# Sheet4.net
KiCad netlist of a schematic drawn in Altium Designer
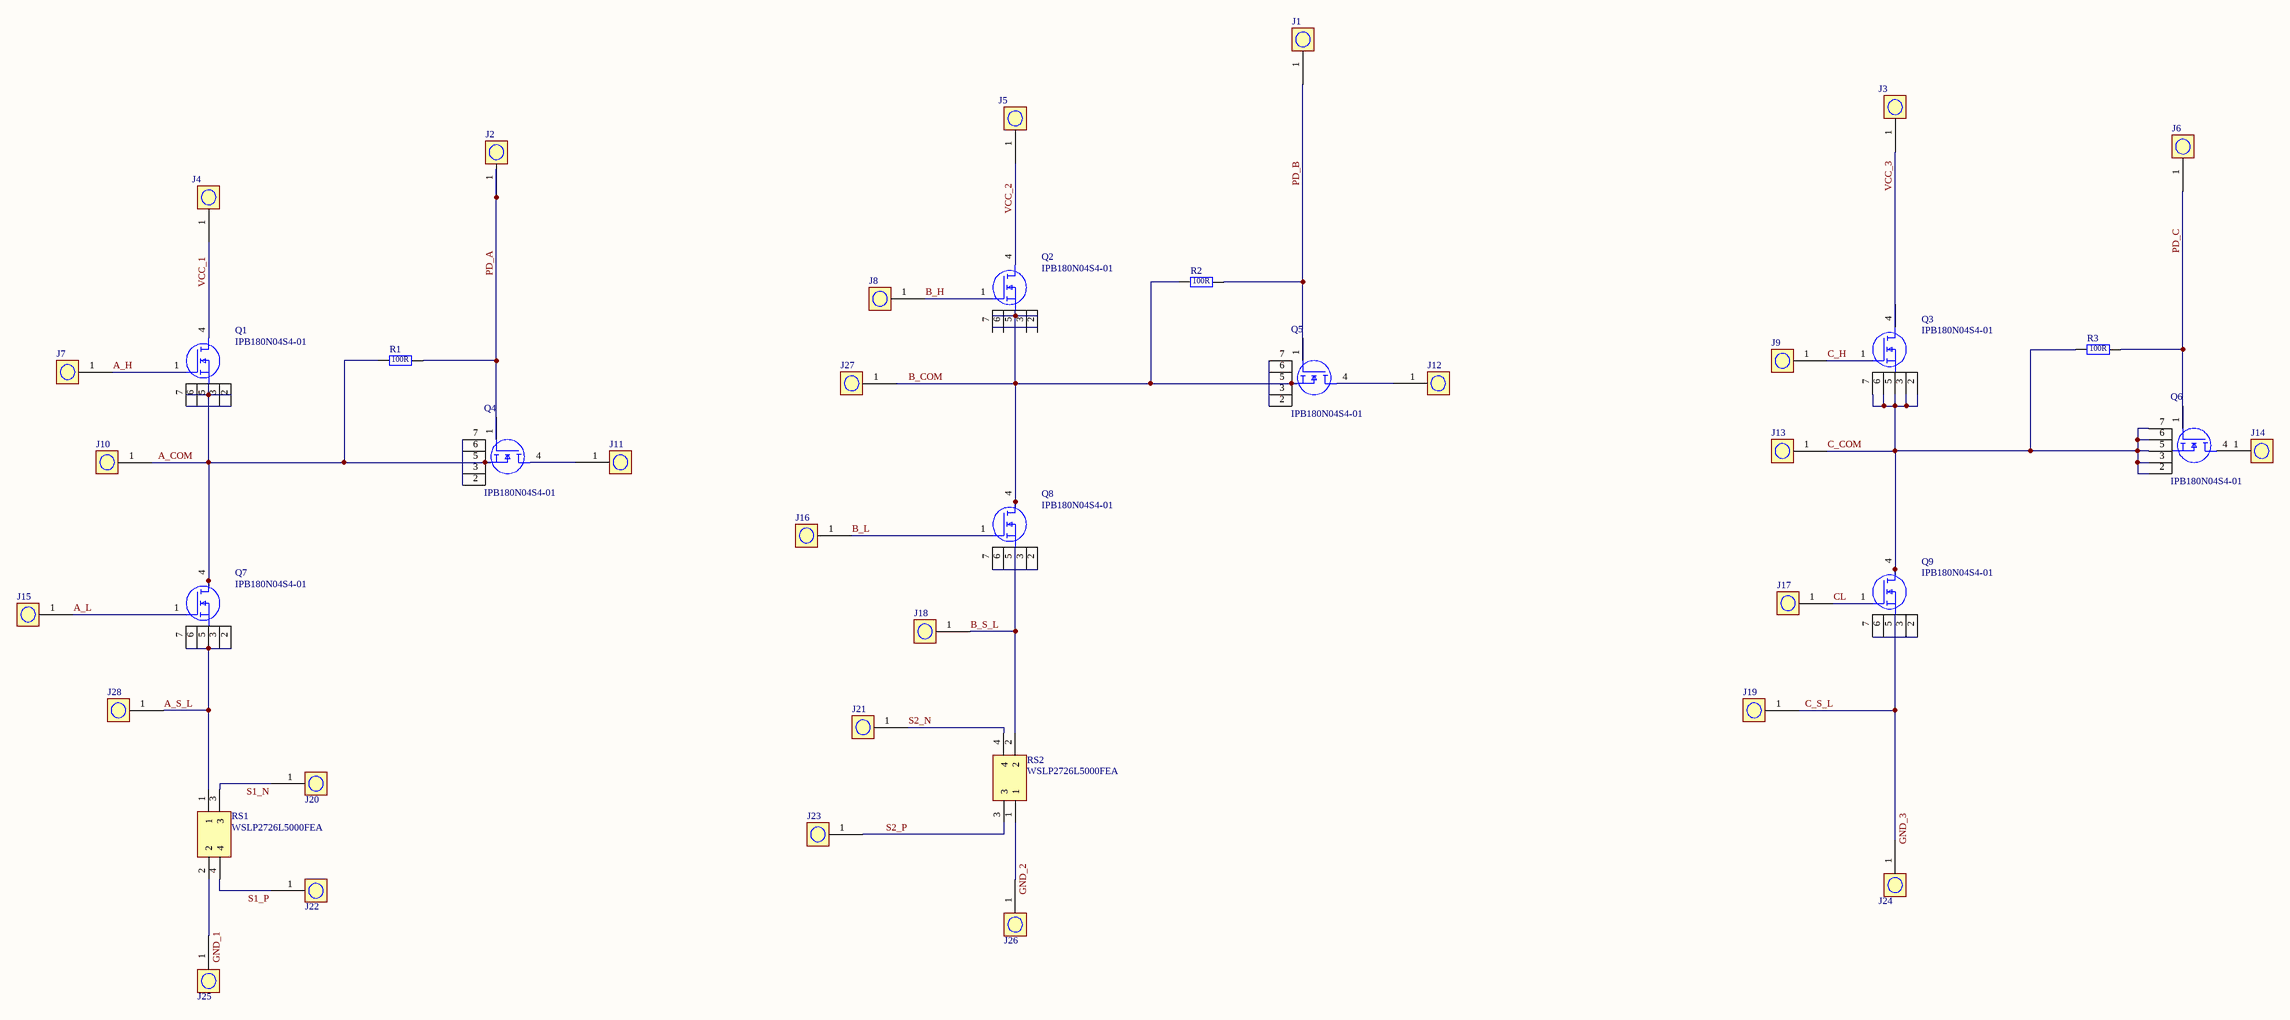
[diagram p0: Sheet4.SchDoc]

(export (version "E")
  (design (tool "Eeschema 10.0.6"))
  (components
    (comp (ref "J1")
      (value "CON_SMD_SMALL")
      (footprint "CONN_SMALL")
      (libsource (lib "") (part "CON_SMD_SMALL_2"))
    )
    (comp (ref "J2")
      (value "CON_SMD_SMALL")
      (footprint "CONN_SMALL")
      (libsource (lib "") (part "CON_SMD_SMALL_2"))
    )
    (comp (ref "J3")
      (value "CON_SMD_SMALL")
      (footprint "CONN_SMALL")
      (libsource (lib "") (part "CON_SMD_SMALL_2"))
    )
    (comp (ref "J4")
      (value "CON_SMD_SMALL")
      (footprint "CONN_SMALL")
      (libsource (lib "") (part "CON_SMD_SMALL_2"))
    )
    (comp (ref "J5")
      (value "CON_SMD_SMALL")
      (footprint "CONN_SMALL")
      (libsource (lib "") (part "CON_SMD_SMALL_2"))
    )
    (comp (ref "J6")
      (value "CON_SMD_SMALL")
      (footprint "CONN_SMALL")
      (libsource (lib "") (part "CON_SMD_SMALL_2"))
    )
    (comp (ref "J7")
      (value "CON_SMD_SMALL")
      (footprint "CONN_SMALL")
      (libsource (lib "") (part "CON_SMD_SMALL_1"))
    )
    (comp (ref "J8")
      (value "CON_SMD_SMALL")
      (footprint "CONN_SMALL")
      (libsource (lib "") (part "CON_SMD_SMALL_1"))
    )
    (comp (ref "J9")
      (value "CON_SMD_SMALL")
      (footprint "CONN_SMALL")
      (libsource (lib "") (part "CON_SMD_SMALL_1"))
    )
    (comp (ref "J10")
      (value "CON_SMD_SMALL")
      (footprint "CONN_SMALL")
      (libsource (lib "") (part "CON_SMD_SMALL_1"))
    )
    (comp (ref "J11")
      (value "CON_SMD_SMALL")
      (footprint "CONN_SMALL")
      (libsource (lib "MyPCBlib") (part "CON_SMD_SMALL"))
    )
    (comp (ref "J12")
      (value "CON_SMD_SMALL")
      (footprint "CONN_SMALL")
      (libsource (lib "MyPCBlib") (part "CON_SMD_SMALL"))
    )
    (comp (ref "J13")
      (value "CON_SMD_SMALL")
      (footprint "CONN_SMALL")
      (libsource (lib "") (part "CON_SMD_SMALL_1"))
    )
    (comp (ref "J14")
      (value "CON_SMD_SMALL")
      (footprint "CONN_SMALL")
      (libsource (lib "MyPCBlib") (part "CON_SMD_SMALL"))
    )
    (comp (ref "J15")
      (value "CON_SMD_SMALL")
      (footprint "CONN_SMALL")
      (libsource (lib "") (part "CON_SMD_SMALL_1"))
    )
    (comp (ref "J16")
      (value "CON_SMD_SMALL")
      (footprint "CONN_SMALL")
      (libsource (lib "") (part "CON_SMD_SMALL_1"))
    )
    (comp (ref "J17")
      (value "CON_SMD_SMALL")
      (footprint "CONN_SMALL")
      (libsource (lib "") (part "CON_SMD_SMALL_1"))
    )
    (comp (ref "J18")
      (value "CON_SMD_SMALL")
      (footprint "CONN_SMALL")
      (libsource (lib "") (part "CON_SMD_SMALL_1"))
    )
    (comp (ref "J19")
      (value "CON_SMD_SMALL")
      (footprint "CONN_SMALL")
      (libsource (lib "") (part "CON_SMD_SMALL_1"))
    )
    (comp (ref "J20")
      (value "CON_SMD_SMALL")
      (footprint "CONN_SMALL")
      (libsource (lib "MyPCBlib") (part "CON_SMD_SMALL"))
    )
    (comp (ref "J21")
      (value "CON_SMD_SMALL")
      (footprint "CONN_SMALL")
      (libsource (lib "") (part "CON_SMD_SMALL_1"))
    )
    (comp (ref "J22")
      (value "CON_SMD_SMALL")
      (footprint "CONN_SMALL")
      (libsource (lib "MyPCBlib") (part "CON_SMD_SMALL"))
    )
    (comp (ref "J23")
      (value "CON_SMD_SMALL")
      (footprint "CONN_SMALL")
      (libsource (lib "") (part "CON_SMD_SMALL_1"))
    )
    (comp (ref "J24")
      (value "CON_SMD_SMALL")
      (footprint "CON_BIG")
      (libsource (lib "") (part "CON_SMD_SMALL_3"))
    )
    (comp (ref "J25")
      (value "CON_SMD_SMALL")
      (footprint "CONN_SMALL")
      (libsource (lib "") (part "CON_SMD_SMALL_3"))
    )
    (comp (ref "J26")
      (value "CON_SMD_SMALL")
      (footprint "CONN_SMALL")
      (libsource (lib "") (part "CON_SMD_SMALL_3"))
    )
    (comp (ref "J27")
      (value "CON_SMD_SMALL")
      (footprint "CONN_SMALL")
      (libsource (lib "") (part "CON_SMD_SMALL_1"))
    )
    (comp (ref "J28")
      (value "CON_SMD_SMALL")
      (footprint "CONN_SMALL")
      (libsource (lib "") (part "CON_SMD_SMALL_1"))
    )
    (comp (ref "Q1")
      (value "IPB180N04S4-01")
      (footprint "SamacSys:IPB240N04S4R9ATMA1")
      (description "MOSFET (N-Channel)")
      (fields (field (name "MOUSER PART NUMBER") "726-IPB180N04S4-01"))
      (libsource (lib "SamacSys") (part "IPB180N04S4-01"))
    )
    (comp (ref "Q2")
      (value "IPB180N04S4-01")
      (footprint "SamacSys:IPB240N04S4R9ATMA1")
      (description "MOSFET (N-Channel)")
      (fields (field (name "MOUSER PART NUMBER") "726-IPB180N04S4-01"))
      (libsource (lib "SamacSys") (part "IPB180N04S4-01"))
    )
    (comp (ref "Q3")
      (value "IPB180N04S4-01")
      (footprint "SamacSys:IPB240N04S4R9ATMA1")
      (description "MOSFET (N-Channel)")
      (fields (field (name "MOUSER PART NUMBER") "726-IPB180N04S4-01"))
      (libsource (lib "SamacSys") (part "IPB180N04S4-01"))
    )
    (comp (ref "Q4")
      (value "IPB180N04S4-01")
      (footprint "SamacSys:IPB240N04S4R9ATMA1")
      (description "MOSFET (N-Channel)")
      (fields (field (name "MOUSER PART NUMBER") "726-IPB180N04S4-01"))
      (libsource (lib "SamacSys") (part "IPB180N04S4-01"))
    )
    (comp (ref "Q5")
      (value "IPB180N04S4-01")
      (footprint "SamacSys:IPB240N04S4R9ATMA1")
      (description "MOSFET (N-Channel)")
      (fields (field (name "MOUSER PART NUMBER") "726-IPB180N04S4-01"))
      (libsource (lib "SamacSys") (part "IPB180N04S4-01"))
    )
    (comp (ref "Q6")
      (value "IPB180N04S4-01")
      (footprint "SamacSys:IPB240N04S4R9ATMA1")
      (description "MOSFET (N-Channel)")
      (fields (field (name "MOUSER PART NUMBER") "726-IPB180N04S4-01"))
      (libsource (lib "SamacSys") (part "IPB180N04S4-01"))
    )
    (comp (ref "Q7")
      (value "IPB180N04S4-01")
      (footprint "SamacSys:IPB240N04S4R9ATMA1")
      (description "MOSFET (N-Channel)")
      (fields (field (name "MOUSER PART NUMBER") "726-IPB180N04S4-01"))
      (libsource (lib "SamacSys") (part "IPB180N04S4-01"))
    )
    (comp (ref "Q8")
      (value "IPB180N04S4-01")
      (footprint "SamacSys:IPB240N04S4R9ATMA1")
      (description "MOSFET (N-Channel)")
      (fields (field (name "MOUSER PART NUMBER") "726-IPB180N04S4-01"))
      (libsource (lib "SamacSys") (part "IPB180N04S4-01"))
    )
    (comp (ref "Q9")
      (value "IPB180N04S4-01")
      (footprint "SamacSys:IPB240N04S4R9ATMA1")
      (description "MOSFET (N-Channel)")
      (fields (field (name "MOUSER PART NUMBER") "726-IPB180N04S4-01"))
      (libsource (lib "SamacSys") (part "IPB180N04S4-01"))
    )
    (comp (ref "R1")
      (value "100R")
      (footprint "RESC1608X06N")
      (fields (field (name "Comment") "R"))
      (libsource (lib "MyPCBlib") (part "R"))
    )
    (comp (ref "R2")
      (value "100R")
      (footprint "RESC1608X06N")
      (fields (field (name "Comment") "R"))
      (libsource (lib "MyPCBlib") (part "R"))
    )
    (comp (ref "R3")
      (value "100R")
      (footprint "RESC1608X06N")
      (fields (field (name "Comment") "R"))
      (libsource (lib "MyPCBlib") (part "R"))
    )
    (comp (ref "RS1")
      (value "WSLP2726L5000FEA")
      (footprint "SamacSys:WSL27261L000FEA")
      (description "Resistor")
      (fields (field (name "MOUSER PART NUMBER") "71-WSLP2726L5000FEA"))
      (libsource (lib "") (part "WSLP2726L5000FEA_1"))
    )
    (comp (ref "RS2")
      (value "WSLP2726L5000FEA")
      (footprint "SamacSys:WSL27261L000FEA")
      (description "Resistor")
      (fields (field (name "MOUSER PART NUMBER") "71-WSLP2726L5000FEA"))
      (libsource (lib "SamacSys") (part "WSLP2726L5000FEA"))
    )
  )
  (nets
    (net (code "1") (name "/A_COM") (class "Default")
      (node (ref "J10") (pin "1") (pinfunction "1_1") (pintype "passive"))
      (node (ref "Q1") (pin "5") (pinfunction "S_3_5") (pintype "passive"))
      (node (ref "Q4") (pin "5") (pinfunction "S_3_5") (pintype "passive"))
      (node (ref "Q7") (pin "4") (pinfunction "D_4") (pintype "passive"))
      (node (ref "R1") (pin "1") (pinfunction "1_1") (pintype "passive"))
    )
    (net (code "2") (name "/A_H") (class "Default")
      (node (ref "J7") (pin "1") (pinfunction "1_1") (pintype "passive"))
      (node (ref "Q1") (pin "1") (pinfunction "G_1") (pintype "passive"))
    )
    (net (code "3") (name "/A_L") (class "Default")
      (node (ref "J15") (pin "1") (pinfunction "1_1") (pintype "passive"))
      (node (ref "Q7") (pin "1") (pinfunction "G_1") (pintype "passive"))
    )
    (net (code "4") (name "/A_S_L") (class "Default")
      (node (ref "J28") (pin "1") (pinfunction "1_1") (pintype "passive"))
      (node (ref "RS1") (pin "1") (pinfunction "1_1") (pintype "passive"))
    )
    (net (code "5") (name "/B_COM") (class "Default")
      (node (ref "J27") (pin "1") (pinfunction "1_1") (pintype "passive"))
      (node (ref "Q2") (pin "5") (pinfunction "S_3_5") (pintype "passive"))
      (node (ref "Q5") (pin "5") (pinfunction "S_3_5") (pintype "passive"))
      (node (ref "Q8") (pin "4") (pinfunction "D_4") (pintype "passive"))
      (node (ref "R2") (pin "1") (pinfunction "1_1") (pintype "passive"))
    )
    (net (code "6") (name "/B_H") (class "Default")
      (node (ref "J8") (pin "1") (pinfunction "1_1") (pintype "passive"))
      (node (ref "Q2") (pin "1") (pinfunction "G_1") (pintype "passive"))
    )
    (net (code "7") (name "/B_L") (class "Default")
      (node (ref "J16") (pin "1") (pinfunction "1_1") (pintype "passive"))
      (node (ref "Q8") (pin "1") (pinfunction "G_1") (pintype "passive"))
    )
    (net (code "8") (name "/B_S_L") (class "Default")
      (node (ref "J18") (pin "1") (pinfunction "1_1") (pintype "passive"))
      (node (ref "Q8") (pin "5") (pinfunction "S_3_5") (pintype "passive"))
      (node (ref "RS2") (pin "2") (pinfunction "2_2") (pintype "passive"))
    )
    (net (code "9") (name "/CL") (class "Default")
      (node (ref "J17") (pin "1") (pinfunction "1_1") (pintype "passive"))
      (node (ref "Q9") (pin "1") (pinfunction "G_1") (pintype "passive"))
    )
    (net (code "10") (name "/C_COM") (class "Default")
      (node (ref "J13") (pin "1") (pinfunction "1_1") (pintype "passive"))
      (node (ref "Q9") (pin "4") (pinfunction "D_4") (pintype "passive"))
      (node (ref "R3") (pin "1") (pinfunction "1_1") (pintype "passive"))
    )
    (net (code "11") (name "/C_H") (class "Default")
      (node (ref "J9") (pin "1") (pinfunction "1_1") (pintype "passive"))
      (node (ref "Q3") (pin "1") (pinfunction "G_1") (pintype "passive"))
    )
    (net (code "12") (name "/C_S_L") (class "Default")
      (node (ref "J19") (pin "1") (pinfunction "1_1") (pintype "passive"))
      (node (ref "J24") (pin "1") (pinfunction "1_1") (pintype "passive"))
      (node (ref "Q9") (pin "5") (pinfunction "S_3_5") (pintype "passive"))
    )
    (net (code "13") (name "/GND_1") (class "Default")
      (node (ref "J25") (pin "1") (pinfunction "1_1") (pintype "passive"))
      (node (ref "RS1") (pin "2") (pinfunction "2_2") (pintype "passive"))
    )
    (net (code "14") (name "/GND_2") (class "Default")
      (node (ref "J26") (pin "1") (pinfunction "1_1") (pintype "passive"))
      (node (ref "RS2") (pin "1") (pinfunction "1_1") (pintype "passive"))
    )
    (net (code "15") (name "/PD_A") (class "Default")
      (node (ref "J2") (pin "1") (pinfunction "1_1") (pintype "passive"))
      (node (ref "Q4") (pin "1") (pinfunction "G_1") (pintype "passive"))
      (node (ref "R1") (pin "2") (pinfunction "2_2") (pintype "passive"))
    )
    (net (code "16") (name "/PD_B") (class "Default")
      (node (ref "J1") (pin "1") (pinfunction "1_1") (pintype "passive"))
      (node (ref "Q5") (pin "1") (pinfunction "G_1") (pintype "passive"))
      (node (ref "R2") (pin "2") (pinfunction "2_2") (pintype "passive"))
    )
    (net (code "17") (name "/PD_C") (class "Default")
      (node (ref "J6") (pin "1") (pinfunction "1_1") (pintype "passive"))
      (node (ref "Q6") (pin "1") (pinfunction "G_1") (pintype "passive"))
      (node (ref "R3") (pin "2") (pinfunction "2_2") (pintype "passive"))
    )
    (net (code "18") (name "/S1_N") (class "Default")
      (node (ref "J20") (pin "1") (pinfunction "1_1") (pintype "passive"))
      (node (ref "RS1") (pin "3") (pinfunction "3_3") (pintype "passive"))
    )
    (net (code "19") (name "/S1_P") (class "Default")
      (node (ref "J22") (pin "1") (pinfunction "1_1") (pintype "passive"))
      (node (ref "RS1") (pin "4") (pinfunction "4_4") (pintype "passive"))
    )
    (net (code "20") (name "/S2_N") (class "Default")
      (node (ref "J21") (pin "1") (pinfunction "1_1") (pintype "passive"))
      (node (ref "RS2") (pin "4") (pinfunction "4_4") (pintype "passive"))
    )
    (net (code "21") (name "/S2_P") (class "Default")
      (node (ref "J23") (pin "1") (pinfunction "1_1") (pintype "passive"))
      (node (ref "RS2") (pin "3") (pinfunction "3_3") (pintype "passive"))
    )
    (net (code "22") (name "/VCC_1") (class "Default")
      (node (ref "J4") (pin "1") (pinfunction "1_1") (pintype "passive"))
      (node (ref "Q1") (pin "4") (pinfunction "D_4") (pintype "passive"))
    )
    (net (code "23") (name "/VCC_2") (class "Default")
      (node (ref "J5") (pin "1") (pinfunction "1_1") (pintype "passive"))
      (node (ref "Q2") (pin "4") (pinfunction "D_4") (pintype "passive"))
    )
    (net (code "24") (name "/VCC_3") (class "Default")
      (node (ref "J3") (pin "1") (pinfunction "1_1") (pintype "passive"))
      (node (ref "Q3") (pin "4") (pinfunction "D_4") (pintype "passive"))
    )
    (net (code "25") (name "Net-(Q4-D)") (class "Default")
      (node (ref "J11") (pin "1") (pinfunction "1_1") (pintype "passive"))
      (node (ref "Q4") (pin "4") (pinfunction "D_4") (pintype "passive"))
    )
    (net (code "26") (name "Net-(Q5-D)") (class "Default")
      (node (ref "J12") (pin "1") (pinfunction "1_1") (pintype "passive"))
      (node (ref "Q5") (pin "4") (pinfunction "D_4") (pintype "passive"))
    )
    (net (code "27") (name "Net-(Q6-D)") (class "Default")
      (node (ref "J14") (pin "1") (pinfunction "1_1") (pintype "passive"))
      (node (ref "Q6") (pin "4") (pinfunction "D_4") (pintype "passive"))
    )
    (net (code "28") (name "unconnected-(Q1-S_1-Pad2)") (class "Default")
      (node (ref "Q1") (pin "2") (pinfunction "S_1_2") (pintype "passive"))
    )
    (net (code "29") (name "unconnected-(Q1-S_2-Pad3)") (class "Default")
      (node (ref "Q1") (pin "3") (pinfunction "S_2_3") (pintype "passive"))
    )
    (net (code "30") (name "unconnected-(Q1-S_4-Pad6)") (class "Default")
      (node (ref "Q1") (pin "6") (pinfunction "S_4_6") (pintype "passive"))
    )
    (net (code "31") (name "unconnected-(Q1-S_5-Pad7)") (class "Default")
      (node (ref "Q1") (pin "7") (pinfunction "S_5_7") (pintype "passive"))
    )
    (net (code "32") (name "unconnected-(Q2-S_1-Pad2)") (class "Default")
      (node (ref "Q2") (pin "2") (pinfunction "S_1_2") (pintype "passive"))
    )
    (net (code "33") (name "unconnected-(Q2-S_2-Pad3)") (class "Default")
      (node (ref "Q2") (pin "3") (pinfunction "S_2_3") (pintype "passive"))
    )
    (net (code "34") (name "unconnected-(Q2-S_4-Pad6)") (class "Default")
      (node (ref "Q2") (pin "6") (pinfunction "S_4_6") (pintype "passive"))
    )
    (net (code "35") (name "unconnected-(Q2-S_5-Pad7)") (class "Default")
      (node (ref "Q2") (pin "7") (pinfunction "S_5_7") (pintype "passive"))
    )
    (net (code "36") (name "unconnected-(Q3-S_1-Pad2)") (class "Default")
      (node (ref "Q3") (pin "2") (pinfunction "S_1_2") (pintype "passive"))
    )
    (net (code "37") (name "unconnected-(Q3-S_2-Pad3)") (class "Default")
      (node (ref "Q3") (pin "3") (pinfunction "S_2_3") (pintype "passive"))
    )
    (net (code "38") (name "unconnected-(Q3-S_3-Pad5)") (class "Default")
      (node (ref "Q3") (pin "5") (pinfunction "S_3_5") (pintype "passive"))
    )
    (net (code "39") (name "unconnected-(Q3-S_4-Pad6)") (class "Default")
      (node (ref "Q3") (pin "6") (pinfunction "S_4_6") (pintype "passive"))
    )
    (net (code "40") (name "unconnected-(Q3-S_5-Pad7)") (class "Default")
      (node (ref "Q3") (pin "7") (pinfunction "S_5_7") (pintype "passive"))
    )
    (net (code "41") (name "unconnected-(Q4-S_1-Pad2)") (class "Default")
      (node (ref "Q4") (pin "2") (pinfunction "S_1_2") (pintype "passive"))
    )
    (net (code "42") (name "unconnected-(Q4-S_2-Pad3)") (class "Default")
      (node (ref "Q4") (pin "3") (pinfunction "S_2_3") (pintype "passive"))
    )
    (net (code "43") (name "unconnected-(Q4-S_4-Pad6)") (class "Default")
      (node (ref "Q4") (pin "6") (pinfunction "S_4_6") (pintype "passive"))
    )
    (net (code "44") (name "unconnected-(Q4-S_5-Pad7)") (class "Default")
      (node (ref "Q4") (pin "7") (pinfunction "S_5_7") (pintype "passive"))
    )
    (net (code "45") (name "unconnected-(Q5-S_1-Pad2)") (class "Default")
      (node (ref "Q5") (pin "2") (pinfunction "S_1_2") (pintype "passive"))
    )
    (net (code "46") (name "unconnected-(Q5-S_2-Pad3)") (class "Default")
      (node (ref "Q5") (pin "3") (pinfunction "S_2_3") (pintype "passive"))
    )
    (net (code "47") (name "unconnected-(Q5-S_4-Pad6)") (class "Default")
      (node (ref "Q5") (pin "6") (pinfunction "S_4_6") (pintype "passive"))
    )
    (net (code "48") (name "unconnected-(Q5-S_5-Pad7)") (class "Default")
      (node (ref "Q5") (pin "7") (pinfunction "S_5_7") (pintype "passive"))
    )
    (net (code "49") (name "unconnected-(Q6-S_1-Pad2)") (class "Default")
      (node (ref "Q6") (pin "2") (pinfunction "S_1_2") (pintype "passive"))
    )
    (net (code "50") (name "unconnected-(Q6-S_2-Pad3)") (class "Default")
      (node (ref "Q6") (pin "3") (pinfunction "S_2_3") (pintype "passive"))
    )
    (net (code "51") (name "unconnected-(Q6-S_3-Pad5)") (class "Default")
      (node (ref "Q6") (pin "5") (pinfunction "S_3_5") (pintype "passive"))
    )
    (net (code "52") (name "unconnected-(Q6-S_4-Pad6)") (class "Default")
      (node (ref "Q6") (pin "6") (pinfunction "S_4_6") (pintype "passive"))
    )
    (net (code "53") (name "unconnected-(Q6-S_5-Pad7)") (class "Default")
      (node (ref "Q6") (pin "7") (pinfunction "S_5_7") (pintype "passive"))
    )
    (net (code "54") (name "unconnected-(Q7-S_1-Pad2)") (class "Default")
      (node (ref "Q7") (pin "2") (pinfunction "S_1_2") (pintype "passive"))
    )
    (net (code "55") (name "unconnected-(Q7-S_2-Pad3)") (class "Default")
      (node (ref "Q7") (pin "3") (pinfunction "S_2_3") (pintype "passive"))
    )
    (net (code "56") (name "unconnected-(Q7-S_3-Pad5)") (class "Default")
      (node (ref "Q7") (pin "5") (pinfunction "S_3_5") (pintype "passive"))
    )
    (net (code "57") (name "unconnected-(Q7-S_4-Pad6)") (class "Default")
      (node (ref "Q7") (pin "6") (pinfunction "S_4_6") (pintype "passive"))
    )
    (net (code "58") (name "unconnected-(Q7-S_5-Pad7)") (class "Default")
      (node (ref "Q7") (pin "7") (pinfunction "S_5_7") (pintype "passive"))
    )
    (net (code "59") (name "unconnected-(Q8-S_1-Pad2)") (class "Default")
      (node (ref "Q8") (pin "2") (pinfunction "S_1_2") (pintype "passive"))
    )
    (net (code "60") (name "unconnected-(Q8-S_2-Pad3)") (class "Default")
      (node (ref "Q8") (pin "3") (pinfunction "S_2_3") (pintype "passive"))
    )
    (net (code "61") (name "unconnected-(Q8-S_4-Pad6)") (class "Default")
      (node (ref "Q8") (pin "6") (pinfunction "S_4_6") (pintype "passive"))
    )
    (net (code "62") (name "unconnected-(Q8-S_5-Pad7)") (class "Default")
      (node (ref "Q8") (pin "7") (pinfunction "S_5_7") (pintype "passive"))
    )
    (net (code "63") (name "unconnected-(Q9-S_1-Pad2)") (class "Default")
      (node (ref "Q9") (pin "2") (pinfunction "S_1_2") (pintype "passive"))
    )
    (net (code "64") (name "unconnected-(Q9-S_2-Pad3)") (class "Default")
      (node (ref "Q9") (pin "3") (pinfunction "S_2_3") (pintype "passive"))
    )
    (net (code "65") (name "unconnected-(Q9-S_4-Pad6)") (class "Default")
      (node (ref "Q9") (pin "6") (pinfunction "S_4_6") (pintype "passive"))
    )
    (net (code "66") (name "unconnected-(Q9-S_5-Pad7)") (class "Default")
      (node (ref "Q9") (pin "7") (pinfunction "S_5_7") (pintype "passive"))
    )
  )
)
